# PowerBoard.net
KiCad netlist of a schematic drawn in EAGLE
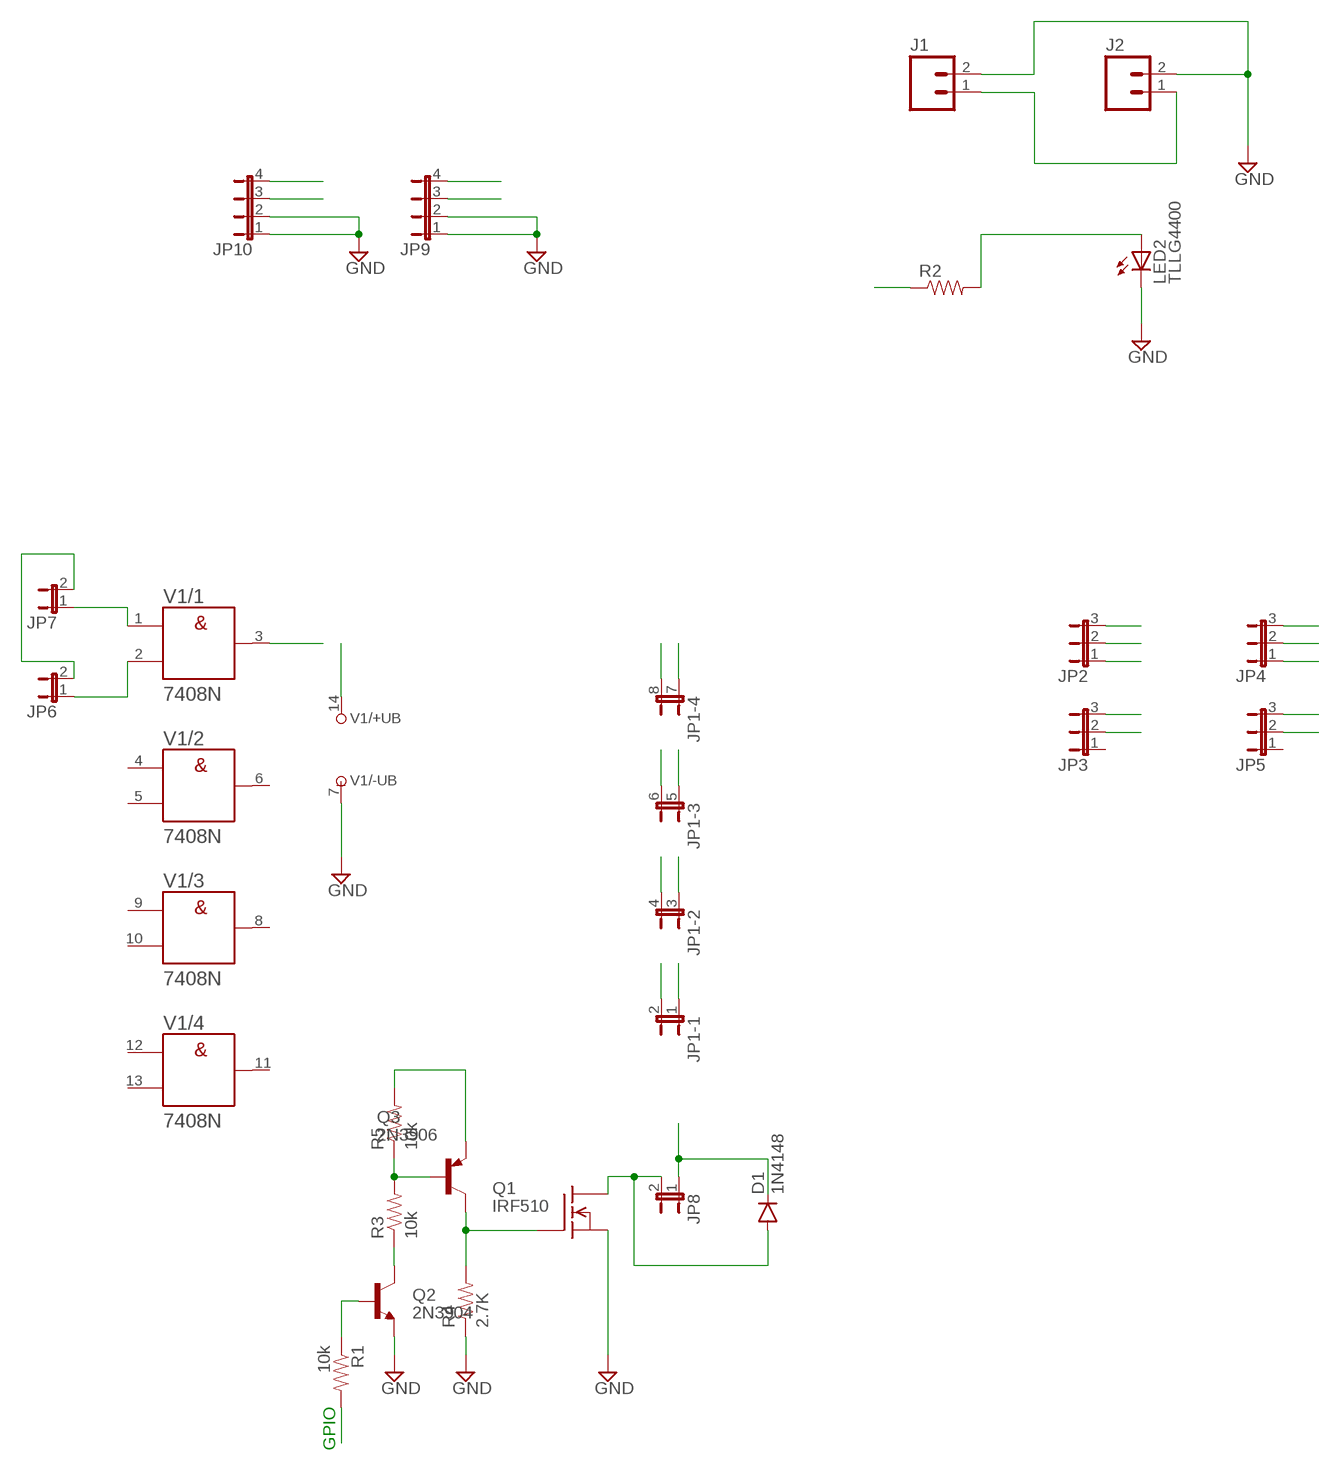
[diagram p0: schematic, sheet 1]

(export (version "E")
  (design (tool "Eeschema 10.0.6"))
  (components
    (comp (ref "D1")
      (value "1N4148")
      (footprint "eagle-import:DIODE-1N4148")
      (libsource (lib "eagle-import") (part "DIODE1N4148"))
    )
    (comp (ref "J1")
      (value "M02JST-PTH-2")
      (footprint "eagle-import:JST-2-PTH")
      (libsource (lib "eagle-import") (part "M02JST-PTH-2"))
    )
    (comp (ref "J2")
      (value "M02JST-PTH-2")
      (footprint "eagle-import:JST-2-PTH")
      (libsource (lib "eagle-import") (part "M02JST-PTH-2"))
    )
    (comp (ref "JP1")
      (value "JP4QE")
      (footprint "eagle-import:JP4Q")
      (libsource (lib "eagle-import") (part "JP4QE"))
    )
    (comp (ref "JP2")
      (value "JP2E")
      (footprint "eagle-import:JP2")
      (libsource (lib "eagle-import") (part "JP2E"))
    )
    (comp (ref "JP3")
      (value "JP2E")
      (footprint "eagle-import:JP2")
      (libsource (lib "eagle-import") (part "JP2E"))
    )
    (comp (ref "JP4")
      (value "JP2E")
      (footprint "eagle-import:JP2")
      (libsource (lib "eagle-import") (part "JP2E"))
    )
    (comp (ref "JP5")
      (value "JP2E")
      (footprint "eagle-import:JP2")
      (libsource (lib "eagle-import") (part "JP2E"))
    )
    (comp (ref "JP6")
      (value "JP1E")
      (footprint "eagle-import:JP1")
      (libsource (lib "eagle-import") (part "JP1E"))
    )
    (comp (ref "JP7")
      (value "JP1E")
      (footprint "eagle-import:JP1")
      (libsource (lib "eagle-import") (part "JP1E"))
    )
    (comp (ref "JP8")
      (value "JP1E")
      (footprint "eagle-import:JP1")
      (libsource (lib "eagle-import") (part "JP1E"))
    )
    (comp (ref "JP9")
      (value "JP4E")
      (footprint "eagle-import:JP4")
      (libsource (lib "eagle-import") (part "JP4E"))
    )
    (comp (ref "JP10")
      (value "JP4E")
      (footprint "eagle-import:JP4")
      (libsource (lib "eagle-import") (part "JP4E"))
    )
    (comp (ref "LED2")
      (value "TLLG4400")
      (footprint "eagle-import:LED3MM")
      (fields (field (name "MF") "VISHAY SEMICONDUCTOR"))
      (libsource (lib "eagle-import") (part "TLLG4400"))
    )
    (comp (ref "Q1")
      (value "IRF510")
      (footprint "eagle-import:TO220")
      (libsource (lib "eagle-import") (part "IRF510"))
    )
    (comp (ref "Q2")
      (value "2N3904")
      (footprint "eagle-import:TO-92")
      (libsource (lib "eagle-import") (part "TRANSISTOR_NPN2N3904"))
    )
    (comp (ref "Q3")
      (value "2N3906")
      (footprint "eagle-import:TO92")
      (libsource (lib "eagle-import") (part "2N3906"))
    )
    (comp (ref "R1")
      (value "10k")
      (footprint "eagle-import:AXIAL-0.4")
      (libsource (lib "eagle-import") (part "SparkFun-Resistors_RESISTORPTH-1/4W"))
    )
    (comp (ref "R2")
      (value "RESISTORPTH-1/4W")
      (footprint "eagle-import:AXIAL-0.4")
      (libsource (lib "eagle-import") (part "SparkFun-Resistors_RESISTORPTH-1/4W"))
    )
    (comp (ref "R3")
      (value "10k")
      (footprint "eagle-import:AXIAL-0.4")
      (libsource (lib "eagle-import") (part "RESISTORPTH-1/4W"))
    )
    (comp (ref "R4")
      (value "2.7K")
      (footprint "eagle-import:AXIAL-0.4")
      (libsource (lib "eagle-import") (part "RESISTORPTH-1/4W"))
    )
    (comp (ref "R5")
      (value "10k")
      (footprint "eagle-import:AXIAL-0.4")
      (libsource (lib "eagle-import") (part "RESISTORPTH-1/4W"))
    )
    (comp (ref "V1")
      (value "7408N")
      (footprint "eagle-import:DIL14")
      (libsource (lib "eagle-import") (part "7408N"))
    )
  )
  (nets
    (net (code "1") (name "/1.8VCC") (class "Default")
      (node (ref "JP1") (pin "3") (pinfunction "1_3") (pintype "passive"))
      (node (ref "JP2") (pin "1") (pinfunction "1_1") (pintype "passive"))
    )
    (net (code "2") (name "/5VCC") (class "Default")
      (node (ref "JP1") (pin "7") (pinfunction "1_7") (pintype "passive"))
      (node (ref "JP10") (pin "3") (pinfunction "3_3") (pintype "passive"))
      (node (ref "JP4") (pin "1") (pinfunction "1_1") (pintype "passive"))
      (node (ref "R2") (pin "P$1") (pinfunction "1_P$1") (pintype "passive"))
      (node (ref "V1") (pin "14") (pinfunction "+UB_14") (pintype "power_in"))
    )
    (net (code "3") (name "/15VCC") (class "Default")
      (node (ref "D1") (pin "C") (pinfunction "C_C") (pintype "passive"))
      (node (ref "J1") (pin "1") (pinfunction "1_1") (pintype "passive"))
      (node (ref "J2") (pin "1") (pinfunction "1_1") (pintype "passive"))
      (node (ref "JP8") (pin "1") (pinfunction "1_1") (pintype "passive"))
      (node (ref "JP9") (pin "3") (pinfunction "3_3") (pintype "passive"))
      (node (ref "Q3") (pin "3") (pinfunction "E_3") (pintype "passive"))
      (node (ref "R5") (pin "P$2") (pinfunction "2_P$2") (pintype "passive"))
    )
    (net (code "4") (name "/HV1") (class "Default")
      (node (ref "JP4") (pin "3") (pinfunction "3_3") (pintype "passive"))
      (node (ref "JP6") (pin "2") (pinfunction "2_2") (pintype "passive"))
      (node (ref "JP7") (pin "2") (pinfunction "2_2") (pintype "passive"))
    )
    (net (code "5") (name "/HV2") (class "Default")
      (node (ref "JP4") (pin "2") (pinfunction "2_2") (pintype "passive"))
      (node (ref "V1") (pin "3") (pinfunction "Y_3") (pintype "output"))
    )
    (net (code "6") (name "/KICKER") (class "Default")
      (node (ref "JP1") (pin "4") (pinfunction "2_4") (pintype "passive"))
      (node (ref "R1") (pin "P$2") (pinfunction "2_P$2") (pintype "passive"))
    )
    (net (code "7") (name "/LV1") (class "Default")
      (node (ref "JP1") (pin "1") (pinfunction "1_1") (pintype "passive"))
      (node (ref "JP2") (pin "3") (pinfunction "3_3") (pintype "passive"))
    )
    (net (code "8") (name "/LV2") (class "Default")
      (node (ref "JP1") (pin "2") (pinfunction "2_2") (pintype "passive"))
      (node (ref "JP2") (pin "2") (pinfunction "2_2") (pintype "passive"))
    )
    (net (code "9") (name "GND") (class "Default")
      (node (ref "J1") (pin "2") (pinfunction "2_2") (pintype "passive"))
      (node (ref "J2") (pin "2") (pinfunction "2_2") (pintype "passive"))
      (node (ref "JP1") (pin "5") (pinfunction "1_5") (pintype "passive"))
      (node (ref "JP10") (pin "1") (pinfunction "1_1") (pintype "passive"))
      (node (ref "JP10") (pin "2") (pinfunction "2_2") (pintype "passive"))
      (node (ref "JP3") (pin "3") (pinfunction "3_3") (pintype "passive"))
      (node (ref "JP5") (pin "3") (pinfunction "3_3") (pintype "passive"))
      (node (ref "JP9") (pin "1") (pinfunction "1_1") (pintype "passive"))
      (node (ref "JP9") (pin "2") (pinfunction "2_2") (pintype "passive"))
      (node (ref "LED2") (pin "K") (pinfunction "C_K") (pintype "passive"))
      (node (ref "Q1") (pin "3") (pinfunction "S_3") (pintype "passive"))
      (node (ref "Q2") (pin "1") (pinfunction "E_1") (pintype "passive"))
      (node (ref "R4") (pin "P$1") (pinfunction "1_P$1") (pintype "passive"))
      (node (ref "V1") (pin "7") (pinfunction "-UB_7") (pintype "power_in"))
    )
    (net (code "10") (name "Net-(Q1-D)") (class "Default")
      (node (ref "D1") (pin "A") (pinfunction "A_A") (pintype "passive"))
      (node (ref "JP8") (pin "2") (pinfunction "2_2") (pintype "passive"))
      (node (ref "Q1") (pin "2") (pinfunction "D_2") (pintype "passive"))
    )
    (net (code "11") (name "Net-(Q1-G)") (class "Default")
      (node (ref "Q1") (pin "1") (pinfunction "G_1") (pintype "passive"))
      (node (ref "Q3") (pin "1") (pinfunction "C_1") (pintype "passive"))
      (node (ref "R4") (pin "P$2") (pinfunction "2_P$2") (pintype "passive"))
    )
    (net (code "12") (name "Net-(Q2-B)") (class "Default")
      (node (ref "Q2") (pin "2") (pinfunction "B_2") (pintype "passive"))
      (node (ref "R1") (pin "P$1") (pinfunction "1_P$1") (pintype "passive"))
    )
    (net (code "13") (name "Net-(Q2-C)") (class "Default")
      (node (ref "Q2") (pin "3") (pinfunction "C_3") (pintype "passive"))
      (node (ref "R3") (pin "P$1") (pinfunction "1_P$1") (pintype "passive"))
    )
    (net (code "14") (name "Net-(Q3-B)") (class "Default")
      (node (ref "Q3") (pin "2") (pinfunction "B_2") (pintype "passive"))
      (node (ref "R3") (pin "P$2") (pinfunction "2_P$2") (pintype "passive"))
      (node (ref "R5") (pin "P$1") (pinfunction "1_P$1") (pintype "passive"))
    )
    (net (code "15") (name "Net-(R2-2)") (class "Default")
      (node (ref "LED2") (pin "A") (pinfunction "A_A") (pintype "passive"))
      (node (ref "R2") (pin "P$2") (pinfunction "2_P$2") (pintype "passive"))
    )
    (net (code "16") (name "Net-(V1C-A)") (class "Default")
      (node (ref "JP7") (pin "1") (pinfunction "1_1") (pintype "passive"))
      (node (ref "V1") (pin "1") (pinfunction "A_1") (pintype "input"))
    )
    (net (code "17") (name "Net-(V1C-B)") (class "Default")
      (node (ref "JP6") (pin "1") (pinfunction "1_1") (pintype "passive"))
      (node (ref "V1") (pin "2") (pinfunction "B_2") (pintype "input"))
    )
    (net (code "18") (name "unconnected-(JP1C-2-Pad6)") (class "Default")
      (node (ref "JP1") (pin "6") (pinfunction "2_6") (pintype "passive"))
    )
    (net (code "19") (name "unconnected-(JP1D-2-Pad8)") (class "Default")
      (node (ref "JP1") (pin "8") (pinfunction "2_8") (pintype "passive"))
    )
    (net (code "20") (name "unconnected-(JP3-Pad1)") (class "Default")
      (node (ref "JP3") (pin "1") (pinfunction "1_1") (pintype "passive"))
    )
    (net (code "21") (name "unconnected-(JP3-Pad2)") (class "Default")
      (node (ref "JP3") (pin "2") (pinfunction "2_2") (pintype "passive"))
    )
    (net (code "22") (name "unconnected-(JP5-Pad1)") (class "Default")
      (node (ref "JP5") (pin "1") (pinfunction "1_1") (pintype "passive"))
    )
    (net (code "23") (name "unconnected-(JP5-Pad2)") (class "Default")
      (node (ref "JP5") (pin "2") (pinfunction "2_2") (pintype "passive"))
    )
    (net (code "24") (name "unconnected-(JP9-Pad4)") (class "Default")
      (node (ref "JP9") (pin "4") (pinfunction "4_4") (pintype "passive"))
    )
    (net (code "25") (name "unconnected-(JP10-Pad4)") (class "Default")
      (node (ref "JP10") (pin "4") (pinfunction "4_4") (pintype "passive"))
    )
    (net (code "26") (name "unconnected-(V1D-A-Pad4)") (class "Default")
      (node (ref "V1") (pin "4") (pinfunction "A_4") (pintype "input"))
    )
    (net (code "27") (name "unconnected-(V1D-B-Pad5)") (class "Default")
      (node (ref "V1") (pin "5") (pinfunction "B_5") (pintype "input"))
    )
    (net (code "28") (name "unconnected-(V1D-Y-Pad6)") (class "Default")
      (node (ref "V1") (pin "6") (pinfunction "Y_6") (pintype "output"))
    )
    (net (code "29") (name "unconnected-(V1E-A-Pad9)") (class "Default")
      (node (ref "V1") (pin "9") (pinfunction "A_9") (pintype "input"))
    )
    (net (code "30") (name "unconnected-(V1E-B-Pad10)") (class "Default")
      (node (ref "V1") (pin "10") (pinfunction "B_10") (pintype "input"))
    )
    (net (code "31") (name "unconnected-(V1E-Y-Pad8)") (class "Default")
      (node (ref "V1") (pin "8") (pinfunction "Y_8") (pintype "output"))
    )
    (net (code "32") (name "unconnected-(V1F-A-Pad12)") (class "Default")
      (node (ref "V1") (pin "12") (pinfunction "A_12") (pintype "input"))
    )
    (net (code "33") (name "unconnected-(V1F-B-Pad13)") (class "Default")
      (node (ref "V1") (pin "13") (pinfunction "B_13") (pintype "input"))
    )
    (net (code "34") (name "unconnected-(V1F-Y-Pad11)") (class "Default")
      (node (ref "V1") (pin "11") (pinfunction "Y_11") (pintype "output"))
    )
  )
)
